# ADC.net
KiCad netlist of a schematic drawn in Altium Designer
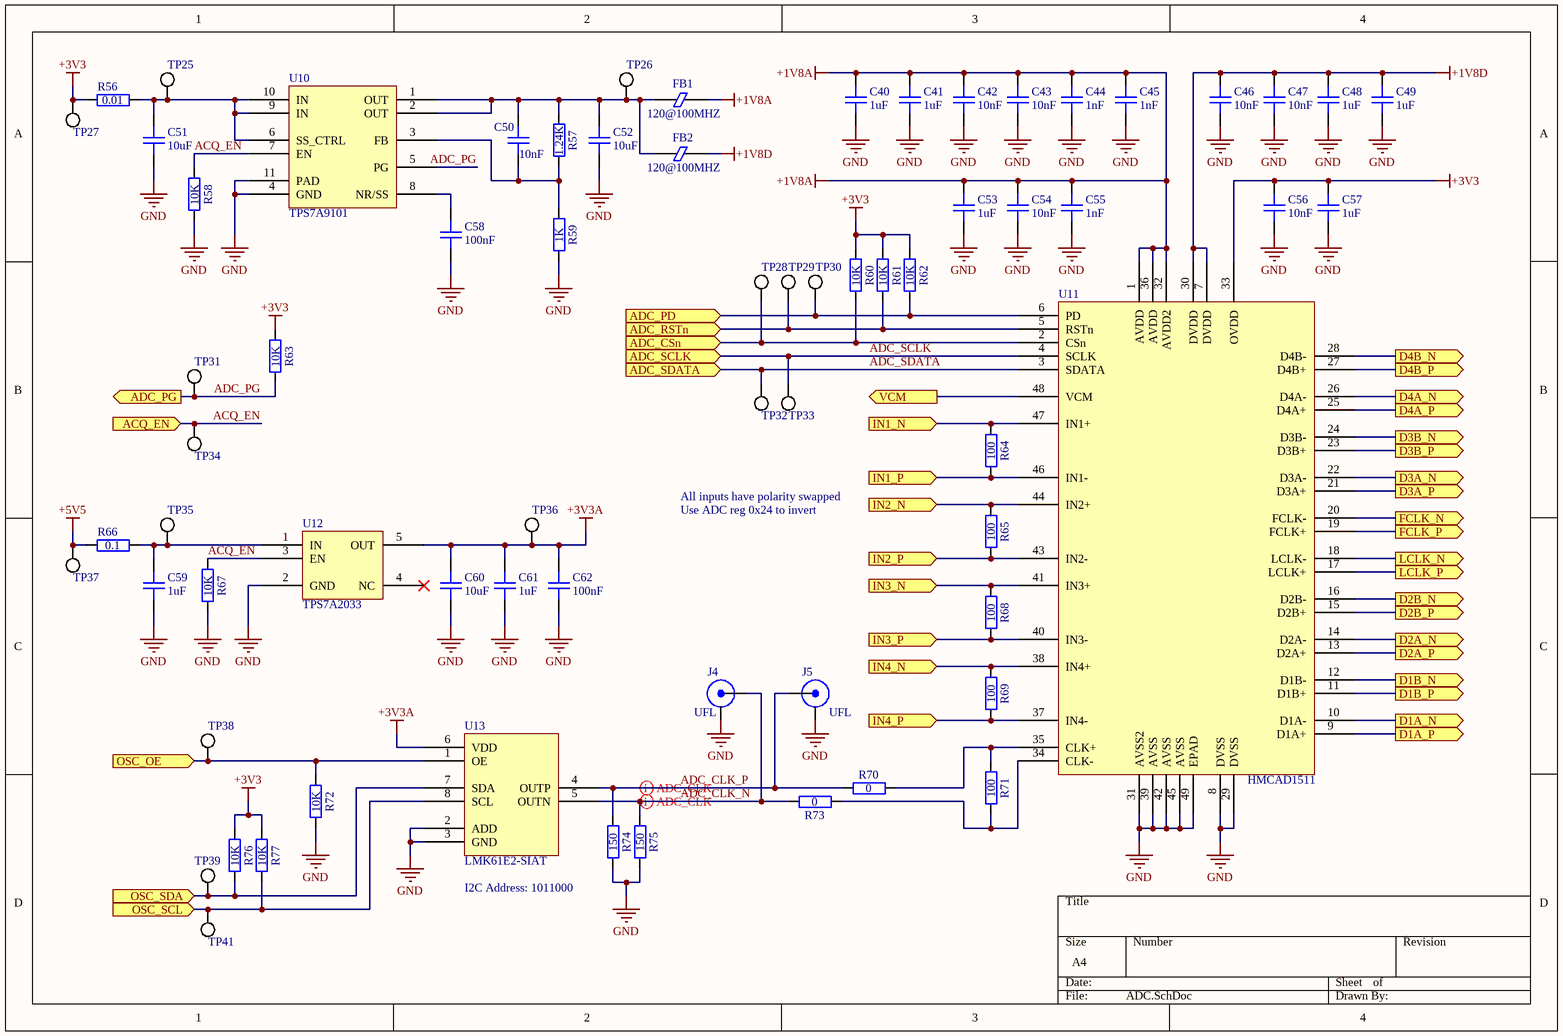
[diagram p0: ADC.SchDoc]

(export (version "E")
  (design (tool "Eeschema 10.0.6"))
  (components
    (comp (ref "C40")
      (value "1uF")
      (footprint "GEN_C_0402")
      (libsource (lib "DSO") (part "CAP 1uF 25V X5R 0402"))
    )
    (comp (ref "C41")
      (value "1uF")
      (footprint "GEN_C_0402")
      (libsource (lib "DSO") (part "CAP 1uF 25V X5R 0402"))
    )
    (comp (ref "C42")
      (value "10nF")
      (footprint "GEN_C_0402")
      (libsource (lib "DSO") (part "CAP 10nF 50V X7R 0402"))
    )
    (comp (ref "C43")
      (value "10nF")
      (footprint "GEN_C_0402")
      (libsource (lib "DSO") (part "CAP 10nF 50V X7R 0402"))
    )
    (comp (ref "C44")
      (value "1nF")
      (footprint "GEN_C_0402")
      (libsource (lib "DSO") (part "CAP 1nF 50V C0G 0402"))
    )
    (comp (ref "C45")
      (value "1nF")
      (footprint "GEN_C_0402")
      (libsource (lib "DSO") (part "CAP 1nF 50V C0G 0402"))
    )
    (comp (ref "C46")
      (value "10nF")
      (footprint "GEN_C_0402")
      (libsource (lib "DSO") (part "CAP 10nF 50V X7R 0402"))
    )
    (comp (ref "C47")
      (value "10nF")
      (footprint "GEN_C_0402")
      (libsource (lib "DSO") (part "CAP 10nF 50V X7R 0402"))
    )
    (comp (ref "C48")
      (value "1uF")
      (footprint "GEN_C_0402")
      (libsource (lib "DSO") (part "CAP 1uF 25V X5R 0402"))
    )
    (comp (ref "C49")
      (value "1uF")
      (footprint "GEN_C_0402")
      (libsource (lib "DSO") (part "CAP 1uF 25V X5R 0402"))
    )
    (comp (ref "C50")
      (value "10nF")
      (footprint "GEN_C_0402")
      (libsource (lib "DSO") (part "CAP 10nF 50V X7R 0402"))
    )
    (comp (ref "C51")
      (value "10uF")
      (footprint "GEN_C_0603")
      (libsource (lib "DSO") (part "CAP 10uF 10V X5R 0603"))
    )
    (comp (ref "C52")
      (value "10uF")
      (footprint "GEN_C_0603")
      (libsource (lib "DSO") (part "CAP 10uF 10V X5R 0603"))
    )
    (comp (ref "C53")
      (value "1uF")
      (footprint "GEN_C_0402")
      (libsource (lib "DSO") (part "CAP 1uF 25V X5R 0402"))
    )
    (comp (ref "C54")
      (value "10nF")
      (footprint "GEN_C_0402")
      (libsource (lib "DSO") (part "CAP 10nF 50V X7R 0402"))
    )
    (comp (ref "C55")
      (value "1nF")
      (footprint "GEN_C_0402")
      (libsource (lib "DSO") (part "CAP 1nF 50V C0G 0402"))
    )
    (comp (ref "C56")
      (value "10nF")
      (footprint "GEN_C_0402")
      (libsource (lib "DSO") (part "CAP 10nF 50V X7R 0402"))
    )
    (comp (ref "C57")
      (value "1uF")
      (footprint "GEN_C_0402")
      (libsource (lib "DSO") (part "CAP 1uF 25V X5R 0402"))
    )
    (comp (ref "C58")
      (value "100nF")
      (footprint "GEN_C_0402")
      (libsource (lib "DSO") (part "CAP 100nF 16V X7R 0402"))
    )
    (comp (ref "C59")
      (value "1uF")
      (footprint "GEN_C_0402")
      (libsource (lib "DSO") (part "CAP 1uF 25V X5R 0402"))
    )
    (comp (ref "C60")
      (value "10uF")
      (footprint "GEN_C_0603")
      (libsource (lib "DSO") (part "CAP 10uF 10V X5R 0603"))
    )
    (comp (ref "C61")
      (value "1uF")
      (footprint "GEN_C_0402")
      (libsource (lib "DSO") (part "CAP 1uF 25V X5R 0402"))
    )
    (comp (ref "C62")
      (value "100nF")
      (footprint "GEN_C_0402")
      (libsource (lib "DSO") (part "CAP 100nF 16V X7R 0402"))
    )
    (comp (ref "FB1")
      (value "120@100MHZ")
      (footprint "GEN_R_0402")
      (libsource (lib "DSO") (part "FERRITE BEAD 120 OHM 0402"))
    )
    (comp (ref "FB2")
      (value "120@100MHZ")
      (footprint "GEN_R_0402")
      (libsource (lib "DSO") (part "FERRITE BEAD 120 OHM 0402"))
    )
    (comp (ref "J4") (value "UFL") (footprint "TE_2334884-1") (libsource (lib "DSO") (part "UFL Jack SMD")))
    (comp (ref "J5") (value "UFL") (footprint "TE_2334884-1") (libsource (lib "DSO") (part "UFL Jack SMD")))
    (comp (ref "R56")
      (value "0.01")
      (footprint "GEN_R_0603")
      (fields (field (name "TOLERANCE") "1%"))
      (libsource (lib "DSO") (part "RES 0.01 OHM 1% 1/4W 0603"))
    )
    (comp (ref "R57")
      (value "1.24K")
      (footprint "GEN_R_0402")
      (fields (field (name "TOLERANCE") "1%"))
      (libsource (lib "DSO") (part "RES 1.24K OHM 1% 1/16W 0402"))
    )
    (comp (ref "R58")
      (value "10K")
      (footprint "GEN_R_0402")
      (fields (field (name "TOLERANCE") "1%"))
      (libsource (lib "DSO") (part "RES 10K OHM 1% 1/10W 0402"))
    )
    (comp (ref "R59")
      (value "1K")
      (footprint "GEN_R_0402")
      (fields (field (name "TOLERANCE") "1%"))
      (libsource (lib "DSO") (part "RES 1K OHM 1% 1/10W 0402"))
    )
    (comp (ref "R60")
      (value "10K")
      (footprint "GEN_R_0402")
      (fields (field (name "TOLERANCE") "1%"))
      (libsource (lib "DSO") (part "RES 10K OHM 1% 1/10W 0402"))
    )
    (comp (ref "R61")
      (value "10K")
      (footprint "GEN_R_0402")
      (fields (field (name "TOLERANCE") "1%"))
      (libsource (lib "DSO") (part "RES 10K OHM 1% 1/10W 0402"))
    )
    (comp (ref "R62")
      (value "10K")
      (footprint "GEN_R_0402")
      (fields (field (name "TOLERANCE") "1%"))
      (libsource (lib "DSO") (part "RES 10K OHM 1% 1/10W 0402"))
    )
    (comp (ref "R63")
      (value "10K")
      (footprint "GEN_R_0402")
      (fields (field (name "TOLERANCE") "1%"))
      (libsource (lib "DSO") (part "RES 10K OHM 1% 1/10W 0402"))
    )
    (comp (ref "R64")
      (value "100")
      (footprint "GEN_R_0402")
      (fields (field (name "TOLERANCE") "1%"))
      (libsource (lib "DSO") (part "RES 100 OHM 1% 1/10W 0402"))
    )
    (comp (ref "R65")
      (value "100")
      (footprint "GEN_R_0402")
      (fields (field (name "TOLERANCE") "1%"))
      (libsource (lib "DSO") (part "RES 100 OHM 1% 1/10W 0402"))
    )
    (comp (ref "R66")
      (value "0.1")
      (footprint "GEN_R_0402")
      (fields (field (name "TOLERANCE") "1%"))
      (libsource (lib "DSO") (part "RES 0.1 OHM 1% 1/6W 0402"))
    )
    (comp (ref "R67")
      (value "10K")
      (footprint "GEN_R_0402")
      (fields (field (name "TOLERANCE") "1%"))
      (libsource (lib "DSO") (part "RES 10K OHM 1% 1/10W 0402"))
    )
    (comp (ref "R68")
      (value "100")
      (footprint "GEN_R_0402")
      (fields (field (name "TOLERANCE") "1%"))
      (libsource (lib "DSO") (part "RES 100 OHM 1% 1/10W 0402"))
    )
    (comp (ref "R69")
      (value "100")
      (footprint "GEN_R_0402")
      (fields (field (name "TOLERANCE") "1%"))
      (libsource (lib "DSO") (part "RES 100 OHM 1% 1/10W 0402"))
    )
    (comp (ref "R70")
      (value "0")
      (footprint "GEN_R_0402")
      (libsource (lib "DSO") (part "RES 0 OHM 1/16W 0402"))
    )
    (comp (ref "R71")
      (value "100")
      (footprint "GEN_R_0402")
      (fields (field (name "TOLERANCE") "1%"))
      (libsource (lib "DSO") (part "RES 100 OHM 1% 1/10W 0402"))
    )
    (comp (ref "R72")
      (value "10K")
      (footprint "GEN_R_0402")
      (fields (field (name "TOLERANCE") "1%"))
      (libsource (lib "DSO") (part "RES 10K OHM 1% 1/10W 0402"))
    )
    (comp (ref "R73")
      (value "0")
      (footprint "GEN_R_0402")
      (libsource (lib "DSO") (part "RES 0 OHM 1/16W 0402"))
    )
    (comp (ref "R74")
      (value "150")
      (footprint "GEN_R_0402")
      (fields (field (name "TOLERANCE") "1%"))
      (libsource (lib "DSO") (part "RES 150 OHM 1% 1/16W 0402"))
    )
    (comp (ref "R75")
      (value "150")
      (footprint "GEN_R_0402")
      (fields (field (name "TOLERANCE") "1%"))
      (libsource (lib "DSO") (part "RES 150 OHM 1% 1/16W 0402"))
    )
    (comp (ref "R76")
      (value "10K")
      (footprint "GEN_R_0402")
      (fields (field (name "TOLERANCE") "1%"))
      (libsource (lib "DSO") (part "RES 10K OHM 1% 1/10W 0402"))
    )
    (comp (ref "R77")
      (value "10K")
      (footprint "GEN_R_0402")
      (fields (field (name "TOLERANCE") "1%"))
      (libsource (lib "DSO") (part "RES 10K OHM 1% 1/10W 0402"))
    )
    (comp (ref "TP25") (value "PCB") (footprint "GEN_TP_PCB") (libsource (lib "DSO") (part "TP PCB 1mm")))
    (comp (ref "TP26") (value "PCB") (footprint "GEN_TP_PCB") (libsource (lib "DSO") (part "TP PCB 1mm")))
    (comp (ref "TP27") (value "PCB") (footprint "GEN_TP_PCB") (libsource (lib "DSO") (part "TP PCB 1mm")))
    (comp (ref "TP28") (value "PCB") (footprint "GEN_TP_PCB") (libsource (lib "DSO") (part "TP PCB 1mm")))
    (comp (ref "TP29") (value "PCB") (footprint "GEN_TP_PCB") (libsource (lib "DSO") (part "TP PCB 1mm")))
    (comp (ref "TP30") (value "PCB") (footprint "GEN_TP_PCB") (libsource (lib "DSO") (part "TP PCB 1mm")))
    (comp (ref "TP31") (value "PCB") (footprint "GEN_TP_PCB") (libsource (lib "DSO") (part "TP PCB 1mm")))
    (comp (ref "TP32") (value "PCB") (footprint "GEN_TP_PCB") (libsource (lib "DSO") (part "TP PCB 1mm")))
    (comp (ref "TP33") (value "PCB") (footprint "GEN_TP_PCB") (libsource (lib "DSO") (part "TP PCB 1mm")))
    (comp (ref "TP34") (value "PCB") (footprint "GEN_TP_PCB") (libsource (lib "DSO") (part "TP PCB 1mm")))
    (comp (ref "TP35") (value "PCB") (footprint "GEN_TP_PCB") (libsource (lib "DSO") (part "TP PCB 1mm")))
    (comp (ref "TP36") (value "PCB") (footprint "GEN_TP_PCB") (libsource (lib "DSO") (part "TP PCB 1mm")))
    (comp (ref "TP37") (value "PCB") (footprint "GEN_TP_PCB") (libsource (lib "DSO") (part "TP PCB 1mm")))
    (comp (ref "TP38") (value "PCB") (footprint "GEN_TP_PCB") (libsource (lib "DSO") (part "TP PCB 1mm")))
    (comp (ref "TP39") (value "PCB") (footprint "GEN_TP_PCB") (libsource (lib "DSO") (part "TP PCB 1mm")))
    (comp (ref "TP41") (value "PCB") (footprint "GEN_TP_PCB") (libsource (lib "DSO") (part "TP PCB 1mm")))
    (comp (ref "U10")
      (value "TPS7A9101")
      (footprint "TI_WSON10_DSK0010A")
      (libsource (lib "DSO") (part "IC LDO TPS7A9101"))
    )
    (comp (ref "U11")
      (value "HMCAD1511")
      (footprint "AD_QFN48_LP7")
      (libsource (lib "DSO") (part "IC ADC HMCAD1511"))
    )
    (comp (ref "U12")
      (value "TPS7A2033")
      (footprint "GEN_SOT23_5_950_2900X1600X1450")
      (libsource (lib "DSO") (part "IC LDO TPS7A2033"))
    )
    (comp (ref "U13")
      (value "LMK61E2-SIAT")
      (footprint "TI_QFM8_SIA0008B")
      (libsource (lib "DSO") (part "IC PROG OSC LMK61E2-SIAT"))
    )
  )
  (nets
    (net (code "1") (name "+1V8A") (class "Default")
      (node (ref "C40") (pin "2") (pinfunction "2_2") (pintype "passive"))
      (node (ref "C41") (pin "2") (pinfunction "2_2") (pintype "passive"))
      (node (ref "C42") (pin "2") (pinfunction "2_2") (pintype "passive"))
      (node (ref "C43") (pin "2") (pinfunction "2_2") (pintype "passive"))
      (node (ref "C44") (pin "2") (pinfunction "2_2") (pintype "passive"))
      (node (ref "C45") (pin "2") (pinfunction "2_2") (pintype "passive"))
      (node (ref "C53") (pin "2") (pinfunction "2_2") (pintype "passive"))
      (node (ref "C54") (pin "2") (pinfunction "2_2") (pintype "passive"))
      (node (ref "C55") (pin "2") (pinfunction "2_2") (pintype "passive"))
      (node (ref "FB1") (pin "2") (pinfunction "2_2") (pintype "passive"))
      (node (ref "U11") (pin "1") (pinfunction "AVDD_1") (pintype "passive"))
      (node (ref "U11") (pin "32") (pinfunction "AVDD2_32") (pintype "passive"))
      (node (ref "U11") (pin "36") (pinfunction "AVDD_36") (pintype "passive"))
    )
    (net (code "2") (name "+1V8D") (class "Default")
      (node (ref "C46") (pin "2") (pinfunction "2_2") (pintype "passive"))
      (node (ref "C47") (pin "2") (pinfunction "2_2") (pintype "passive"))
      (node (ref "C48") (pin "2") (pinfunction "2_2") (pintype "passive"))
      (node (ref "C49") (pin "2") (pinfunction "2_2") (pintype "passive"))
      (node (ref "FB2") (pin "2") (pinfunction "2_2") (pintype "passive"))
      (node (ref "U11") (pin "30") (pinfunction "DVDD_30") (pintype "passive"))
      (node (ref "U11") (pin "7") (pinfunction "DVDD_7") (pintype "passive"))
    )
    (net (code "3") (name "+3V3") (class "Default")
      (node (ref "C56") (pin "2") (pinfunction "2_2") (pintype "passive"))
      (node (ref "C57") (pin "2") (pinfunction "2_2") (pintype "passive"))
      (node (ref "R56") (pin "1") (pinfunction "1_1") (pintype "passive"))
      (node (ref "R60") (pin "2") (pinfunction "2_2") (pintype "passive"))
      (node (ref "R61") (pin "2") (pinfunction "2_2") (pintype "passive"))
      (node (ref "R62") (pin "2") (pinfunction "2_2") (pintype "passive"))
      (node (ref "R63") (pin "2") (pinfunction "2_2") (pintype "passive"))
      (node (ref "R76") (pin "2") (pinfunction "2_2") (pintype "passive"))
      (node (ref "R77") (pin "2") (pinfunction "2_2") (pintype "passive"))
      (node (ref "TP27") (pin "1") (pinfunction "1_1") (pintype "passive"))
      (node (ref "U11") (pin "33") (pinfunction "OVDD_33") (pintype "passive"))
    )
    (net (code "4") (name "+3V3A") (class "Default")
      (node (ref "C60") (pin "2") (pinfunction "2_2") (pintype "passive"))
      (node (ref "C61") (pin "2") (pinfunction "2_2") (pintype "passive"))
      (node (ref "C62") (pin "2") (pinfunction "2_2") (pintype "passive"))
      (node (ref "TP36") (pin "1") (pinfunction "1_1") (pintype "passive"))
      (node (ref "U12") (pin "5") (pinfunction "OUT_5") (pintype "power_in"))
      (node (ref "U13") (pin "6") (pinfunction "VDD_6") (pintype "power_in"))
    )
    (net (code "5") (name "+5V5") (class "Default")
      (node (ref "R66") (pin "1") (pinfunction "1_1") (pintype "passive"))
      (node (ref "TP37") (pin "1") (pinfunction "1_1") (pintype "passive"))
    )
    (net (code "6") (name "/ACQ_EN") (class "Default")
      (node (ref "R58") (pin "2") (pinfunction "2_2") (pintype "passive"))
      (node (ref "R67") (pin "2") (pinfunction "2_2") (pintype "passive"))
      (node (ref "TP34") (pin "1") (pinfunction "1_1") (pintype "passive"))
      (node (ref "U10") (pin "7") (pinfunction "EN_7") (pintype "passive"))
      (node (ref "U12") (pin "3") (pinfunction "EN_3") (pintype "passive"))
    )
    (net (code "7") (name "/ADC_CLK_N") (class "Default")
      (node (ref "J4") (pin "1") (pinfunction "Signal_1") (pintype "passive"))
      (node (ref "R73") (pin "1") (pinfunction "1_1") (pintype "passive"))
      (node (ref "R75") (pin "2") (pinfunction "2_2") (pintype "passive"))
      (node (ref "U13") (pin "5") (pinfunction "OUTN_5") (pintype "passive"))
    )
    (net (code "8") (name "/ADC_CLK_P") (class "Default")
      (node (ref "J5") (pin "1") (pinfunction "Signal_1") (pintype "passive"))
      (node (ref "R70") (pin "1") (pinfunction "1_1") (pintype "passive"))
      (node (ref "R74") (pin "2") (pinfunction "2_2") (pintype "passive"))
      (node (ref "U13") (pin "4") (pinfunction "OUTP_4") (pintype "passive"))
    )
    (net (code "9") (name "/ADC_CSn") (class "Default")
      (node (ref "R60") (pin "1") (pinfunction "1_1") (pintype "passive"))
      (node (ref "TP28") (pin "1") (pinfunction "1_1") (pintype "passive"))
      (node (ref "U11") (pin "2") (pinfunction "CSn_2") (pintype "passive"))
    )
    (net (code "10") (name "/ADC_PD") (class "Default")
      (node (ref "R62") (pin "1") (pinfunction "1_1") (pintype "passive"))
      (node (ref "TP30") (pin "1") (pinfunction "1_1") (pintype "passive"))
      (node (ref "U11") (pin "6") (pinfunction "PD_6") (pintype "passive"))
    )
    (net (code "11") (name "/ADC_PG") (class "Default")
      (node (ref "R63") (pin "1") (pinfunction "1_1") (pintype "passive"))
      (node (ref "TP31") (pin "1") (pinfunction "1_1") (pintype "passive"))
      (node (ref "U10") (pin "5") (pinfunction "PG_5") (pintype "passive"))
    )
    (net (code "12") (name "/ADC_RSTn") (class "Default")
      (node (ref "R61") (pin "1") (pinfunction "1_1") (pintype "passive"))
      (node (ref "TP29") (pin "1") (pinfunction "1_1") (pintype "passive"))
      (node (ref "U11") (pin "5") (pinfunction "RSTn_5") (pintype "passive"))
    )
    (net (code "13") (name "/ADC_SCLK") (class "Default")
      (node (ref "TP33") (pin "1") (pinfunction "1_1") (pintype "passive"))
      (node (ref "U11") (pin "4") (pinfunction "SCLK_4") (pintype "passive"))
    )
    (net (code "14") (name "/ADC_SDATA") (class "Default")
      (node (ref "TP32") (pin "1") (pinfunction "1_1") (pintype "passive"))
      (node (ref "U11") (pin "3") (pinfunction "SDATA_3") (pintype "passive"))
    )
    (net (code "15") (name "/D1A_N") (class "Default")
      (node (ref "U11") (pin "10") (pinfunction "D1A-_10") (pintype "passive"))
    )
    (net (code "16") (name "/D1A_P") (class "Default")
      (node (ref "U11") (pin "9") (pinfunction "D1A+_9") (pintype "passive"))
    )
    (net (code "17") (name "/D1B_N") (class "Default")
      (node (ref "U11") (pin "12") (pinfunction "D1B-_12") (pintype "passive"))
    )
    (net (code "18") (name "/D1B_P") (class "Default")
      (node (ref "U11") (pin "11") (pinfunction "D1B+_11") (pintype "passive"))
    )
    (net (code "19") (name "/D2A_N") (class "Default")
      (node (ref "U11") (pin "14") (pinfunction "D2A-_14") (pintype "passive"))
    )
    (net (code "20") (name "/D2A_P") (class "Default")
      (node (ref "U11") (pin "13") (pinfunction "D2A+_13") (pintype "passive"))
    )
    (net (code "21") (name "/D2B_N") (class "Default")
      (node (ref "U11") (pin "16") (pinfunction "D2B-_16") (pintype "passive"))
    )
    (net (code "22") (name "/D2B_P") (class "Default")
      (node (ref "U11") (pin "15") (pinfunction "D2B+_15") (pintype "passive"))
    )
    (net (code "23") (name "/D3A_N") (class "Default")
      (node (ref "U11") (pin "22") (pinfunction "D3A-_22") (pintype "passive"))
    )
    (net (code "24") (name "/D3A_P") (class "Default")
      (node (ref "U11") (pin "21") (pinfunction "D3A+_21") (pintype "passive"))
    )
    (net (code "25") (name "/D3B_N") (class "Default")
      (node (ref "U11") (pin "24") (pinfunction "D3B-_24") (pintype "passive"))
    )
    (net (code "26") (name "/D3B_P") (class "Default")
      (node (ref "U11") (pin "23") (pinfunction "D3B+_23") (pintype "passive"))
    )
    (net (code "27") (name "/D4A_N") (class "Default")
      (node (ref "U11") (pin "26") (pinfunction "D4A-_26") (pintype "passive"))
    )
    (net (code "28") (name "/D4A_P") (class "Default")
      (node (ref "U11") (pin "25") (pinfunction "D4A+_25") (pintype "passive"))
    )
    (net (code "29") (name "/D4B_N") (class "Default")
      (node (ref "U11") (pin "28") (pinfunction "D4B-_28") (pintype "passive"))
    )
    (net (code "30") (name "/D4B_P") (class "Default")
      (node (ref "U11") (pin "27") (pinfunction "D4B+_27") (pintype "passive"))
    )
    (net (code "31") (name "/FCLK_N") (class "Default")
      (node (ref "U11") (pin "20") (pinfunction "FCLK-_20") (pintype "passive"))
    )
    (net (code "32") (name "/FCLK_P") (class "Default")
      (node (ref "U11") (pin "19") (pinfunction "FCLK+_19") (pintype "passive"))
    )
    (net (code "33") (name "/IN1_N") (class "Default")
      (node (ref "R64") (pin "2") (pinfunction "2_2") (pintype "passive"))
      (node (ref "U11") (pin "47") (pinfunction "IN1+_47") (pintype "passive"))
    )
    (net (code "34") (name "/IN1_P") (class "Default")
      (node (ref "R64") (pin "1") (pinfunction "1_1") (pintype "passive"))
      (node (ref "U11") (pin "46") (pinfunction "IN1-_46") (pintype "passive"))
    )
    (net (code "35") (name "/IN2_N") (class "Default")
      (node (ref "R65") (pin "2") (pinfunction "2_2") (pintype "passive"))
      (node (ref "U11") (pin "44") (pinfunction "IN2+_44") (pintype "passive"))
    )
    (net (code "36") (name "/IN2_P") (class "Default")
      (node (ref "R65") (pin "1") (pinfunction "1_1") (pintype "passive"))
      (node (ref "U11") (pin "43") (pinfunction "IN2-_43") (pintype "passive"))
    )
    (net (code "37") (name "/IN3_N") (class "Default")
      (node (ref "R68") (pin "2") (pinfunction "2_2") (pintype "passive"))
      (node (ref "U11") (pin "41") (pinfunction "IN3+_41") (pintype "passive"))
    )
    (net (code "38") (name "/IN3_P") (class "Default")
      (node (ref "R68") (pin "1") (pinfunction "1_1") (pintype "passive"))
      (node (ref "U11") (pin "40") (pinfunction "IN3-_40") (pintype "passive"))
    )
    (net (code "39") (name "/IN4_N") (class "Default")
      (node (ref "R69") (pin "2") (pinfunction "2_2") (pintype "passive"))
      (node (ref "U11") (pin "38") (pinfunction "IN4+_38") (pintype "passive"))
    )
    (net (code "40") (name "/IN4_P") (class "Default")
      (node (ref "R69") (pin "1") (pinfunction "1_1") (pintype "passive"))
      (node (ref "U11") (pin "37") (pinfunction "IN4-_37") (pintype "passive"))
    )
    (net (code "41") (name "/LCLK_N") (class "Default")
      (node (ref "U11") (pin "18") (pinfunction "LCLK-_18") (pintype "passive"))
    )
    (net (code "42") (name "/LCLK_P") (class "Default")
      (node (ref "U11") (pin "17") (pinfunction "LCLK+_17") (pintype "passive"))
    )
    (net (code "43") (name "/OSC_OE") (class "Default")
      (node (ref "R72") (pin "2") (pinfunction "2_2") (pintype "passive"))
      (node (ref "TP38") (pin "1") (pinfunction "1_1") (pintype "passive"))
      (node (ref "U13") (pin "1") (pinfunction "OE_1") (pintype "passive"))
    )
    (net (code "44") (name "/OSC_SCL") (class "Default")
      (node (ref "R77") (pin "1") (pinfunction "1_1") (pintype "passive"))
      (node (ref "TP41") (pin "1") (pinfunction "1_1") (pintype "passive"))
      (node (ref "U13") (pin "8") (pinfunction "SCL_8") (pintype "passive"))
    )
    (net (code "45") (name "/OSC_SDA") (class "Default")
      (node (ref "R76") (pin "1") (pinfunction "1_1") (pintype "passive"))
      (node (ref "TP39") (pin "1") (pinfunction "1_1") (pintype "passive"))
      (node (ref "U13") (pin "7") (pinfunction "SDA_7") (pintype "passive"))
    )
    (net (code "46") (name "/VCM") (class "Default")
      (node (ref "U11") (pin "48") (pinfunction "VCM_48") (pintype "passive"))
    )
    (net (code "47") (name "GND") (class "Default")
      (node (ref "C40") (pin "1") (pinfunction "1_1") (pintype "passive"))
      (node (ref "C41") (pin "1") (pinfunction "1_1") (pintype "passive"))
      (node (ref "C42") (pin "1") (pinfunction "1_1") (pintype "passive"))
      (node (ref "C43") (pin "1") (pinfunction "1_1") (pintype "passive"))
      (node (ref "C44") (pin "1") (pinfunction "1_1") (pintype "passive"))
      (node (ref "C45") (pin "1") (pinfunction "1_1") (pintype "passive"))
      (node (ref "C46") (pin "1") (pinfunction "1_1") (pintype "passive"))
      (node (ref "C47") (pin "1") (pinfunction "1_1") (pintype "passive"))
      (node (ref "C48") (pin "1") (pinfunction "1_1") (pintype "passive"))
      (node (ref "C49") (pin "1") (pinfunction "1_1") (pintype "passive"))
      (node (ref "C51") (pin "1") (pinfunction "1_1") (pintype "passive"))
      (node (ref "C52") (pin "1") (pinfunction "1_1") (pintype "passive"))
      (node (ref "C53") (pin "1") (pinfunction "1_1") (pintype "passive"))
      (node (ref "C54") (pin "1") (pinfunction "1_1") (pintype "passive"))
      (node (ref "C55") (pin "1") (pinfunction "1_1") (pintype "passive"))
      (node (ref "C56") (pin "1") (pinfunction "1_1") (pintype "passive"))
      (node (ref "C57") (pin "1") (pinfunction "1_1") (pintype "passive"))
      (node (ref "C58") (pin "1") (pinfunction "1_1") (pintype "passive"))
      (node (ref "C59") (pin "1") (pinfunction "1_1") (pintype "passive"))
      (node (ref "C60") (pin "1") (pinfunction "1_1") (pintype "passive"))
      (node (ref "C61") (pin "1") (pinfunction "1_1") (pintype "passive"))
      (node (ref "C62") (pin "1") (pinfunction "1_1") (pintype "passive"))
      (node (ref "J4") (pin "2") (pinfunction "SHIELD_2") (pintype "passive"))
      (node (ref "J5") (pin "2") (pinfunction "SHIELD_2") (pintype "passive"))
      (node (ref "R58") (pin "1") (pinfunction "1_1") (pintype "passive"))
      (node (ref "R59") (pin "1") (pinfunction "1_1") (pintype "passive"))
      (node (ref "R67") (pin "1") (pinfunction "1_1") (pintype "passive"))
      (node (ref "R72") (pin "1") (pinfunction "1_1") (pintype "passive"))
      (node (ref "R74") (pin "1") (pinfunction "1_1") (pintype "passive"))
      (node (ref "R75") (pin "1") (pinfunction "1_1") (pintype "passive"))
      (node (ref "U10") (pin "11") (pinfunction "PAD_11") (pintype "passive"))
      (node (ref "U10") (pin "4") (pinfunction "GND_4") (pintype "power_in"))
      (node (ref "U11") (pin "29") (pinfunction "DVSS_29") (pintype "passive"))
      (node (ref "U11") (pin "31") (pinfunction "AVSS2_31") (pintype "passive"))
      (node (ref "U11") (pin "39") (pinfunction "AVSS_39") (pintype "passive"))
      (node (ref "U11") (pin "42") (pinfunction "AVSS_42") (pintype "passive"))
      (node (ref "U11") (pin "45") (pinfunction "AVSS_45") (pintype "passive"))
      (node (ref "U11") (pin "49") (pinfunction "EPAD_49") (pintype "passive"))
      (node (ref "U11") (pin "8") (pinfunction "DVSS_8") (pintype "passive"))
      (node (ref "U12") (pin "2") (pinfunction "GND_2") (pintype "power_in"))
      (node (ref "U13") (pin "2") (pinfunction "ADD_2") (pintype "passive"))
      (node (ref "U13") (pin "3") (pinfunction "GND_3") (pintype "power_in"))
    )
    (net (code "48") (name "Net-(C50-Pad2)") (class "Default")
      (node (ref "C50") (pin "2") (pinfunction "2_2") (pintype "passive"))
      (node (ref "C52") (pin "2") (pinfunction "2_2") (pintype "passive"))
      (node (ref "FB1") (pin "1") (pinfunction "1_1") (pintype "passive"))
      (node (ref "FB2") (pin "1") (pinfunction "1_1") (pintype "passive"))
      (node (ref "R57") (pin "2") (pinfunction "2_2") (pintype "passive"))
      (node (ref "TP26") (pin "1") (pinfunction "1_1") (pintype "passive"))
      (node (ref "U10") (pin "1") (pinfunction "OUT_1") (pintype "power_in"))
      (node (ref "U10") (pin "2") (pinfunction "OUT_2") (pintype "power_in"))
    )
    (net (code "49") (name "Net-(U10-FB)") (class "Default")
      (node (ref "C50") (pin "1") (pinfunction "1_1") (pintype "passive"))
      (node (ref "R57") (pin "1") (pinfunction "1_1") (pintype "passive"))
      (node (ref "R59") (pin "2") (pinfunction "2_2") (pintype "passive"))
      (node (ref "U10") (pin "3") (pinfunction "FB_3") (pintype "passive"))
    )
    (net (code "50") (name "Net-(U10-NR{slash}SS)") (class "Default")
      (node (ref "C58") (pin "2") (pinfunction "2_2") (pintype "passive"))
      (node (ref "U10") (pin "8") (pinfunction "NR/SS_8") (pintype "passive"))
    )
    (net (code "51") (name "Net-(U10-SS_CTRL)") (class "Default")
      (node (ref "C51") (pin "2") (pinfunction "2_2") (pintype "passive"))
      (node (ref "R56") (pin "2") (pinfunction "2_2") (pintype "passive"))
      (node (ref "TP25") (pin "1") (pinfunction "1_1") (pintype "passive"))
      (node (ref "U10") (pin "10") (pinfunction "IN_10") (pintype "power_in"))
      (node (ref "U10") (pin "6") (pinfunction "SS_CTRL_6") (pintype "passive"))
      (node (ref "U10") (pin "9") (pinfunction "IN_9") (pintype "power_in"))
    )
    (net (code "52") (name "Net-(U11-CLK+)") (class "Default")
      (node (ref "R70") (pin "2") (pinfunction "2_2") (pintype "passive"))
      (node (ref "R71") (pin "2") (pinfunction "2_2") (pintype "passive"))
      (node (ref "U11") (pin "35") (pinfunction "CLK+_35") (pintype "passive"))
    )
    (net (code "53") (name "Net-(U11-CLK-)") (class "Default")
      (node (ref "R71") (pin "1") (pinfunction "1_1") (pintype "passive"))
      (node (ref "R73") (pin "2") (pinfunction "2_2") (pintype "passive"))
      (node (ref "U11") (pin "34") (pinfunction "CLK-_34") (pintype "passive"))
    )
    (net (code "54") (name "Net-(U12-IN)") (class "Default")
      (node (ref "C59") (pin "2") (pinfunction "2_2") (pintype "passive"))
      (node (ref "R66") (pin "2") (pinfunction "2_2") (pintype "passive"))
      (node (ref "TP35") (pin "1") (pinfunction "1_1") (pintype "passive"))
      (node (ref "U12") (pin "1") (pinfunction "IN_1") (pintype "power_in"))
    )
    (net (code "55") (name "unconnected-(U12-NC-Pad4)") (class "Default")
      (node (ref "U12") (pin "4") (pinfunction "NC_4") (pintype "passive+no_connect"))
    )
  )
)
